# Sheet1.net
KiCad netlist of a schematic drawn in Altium Designer
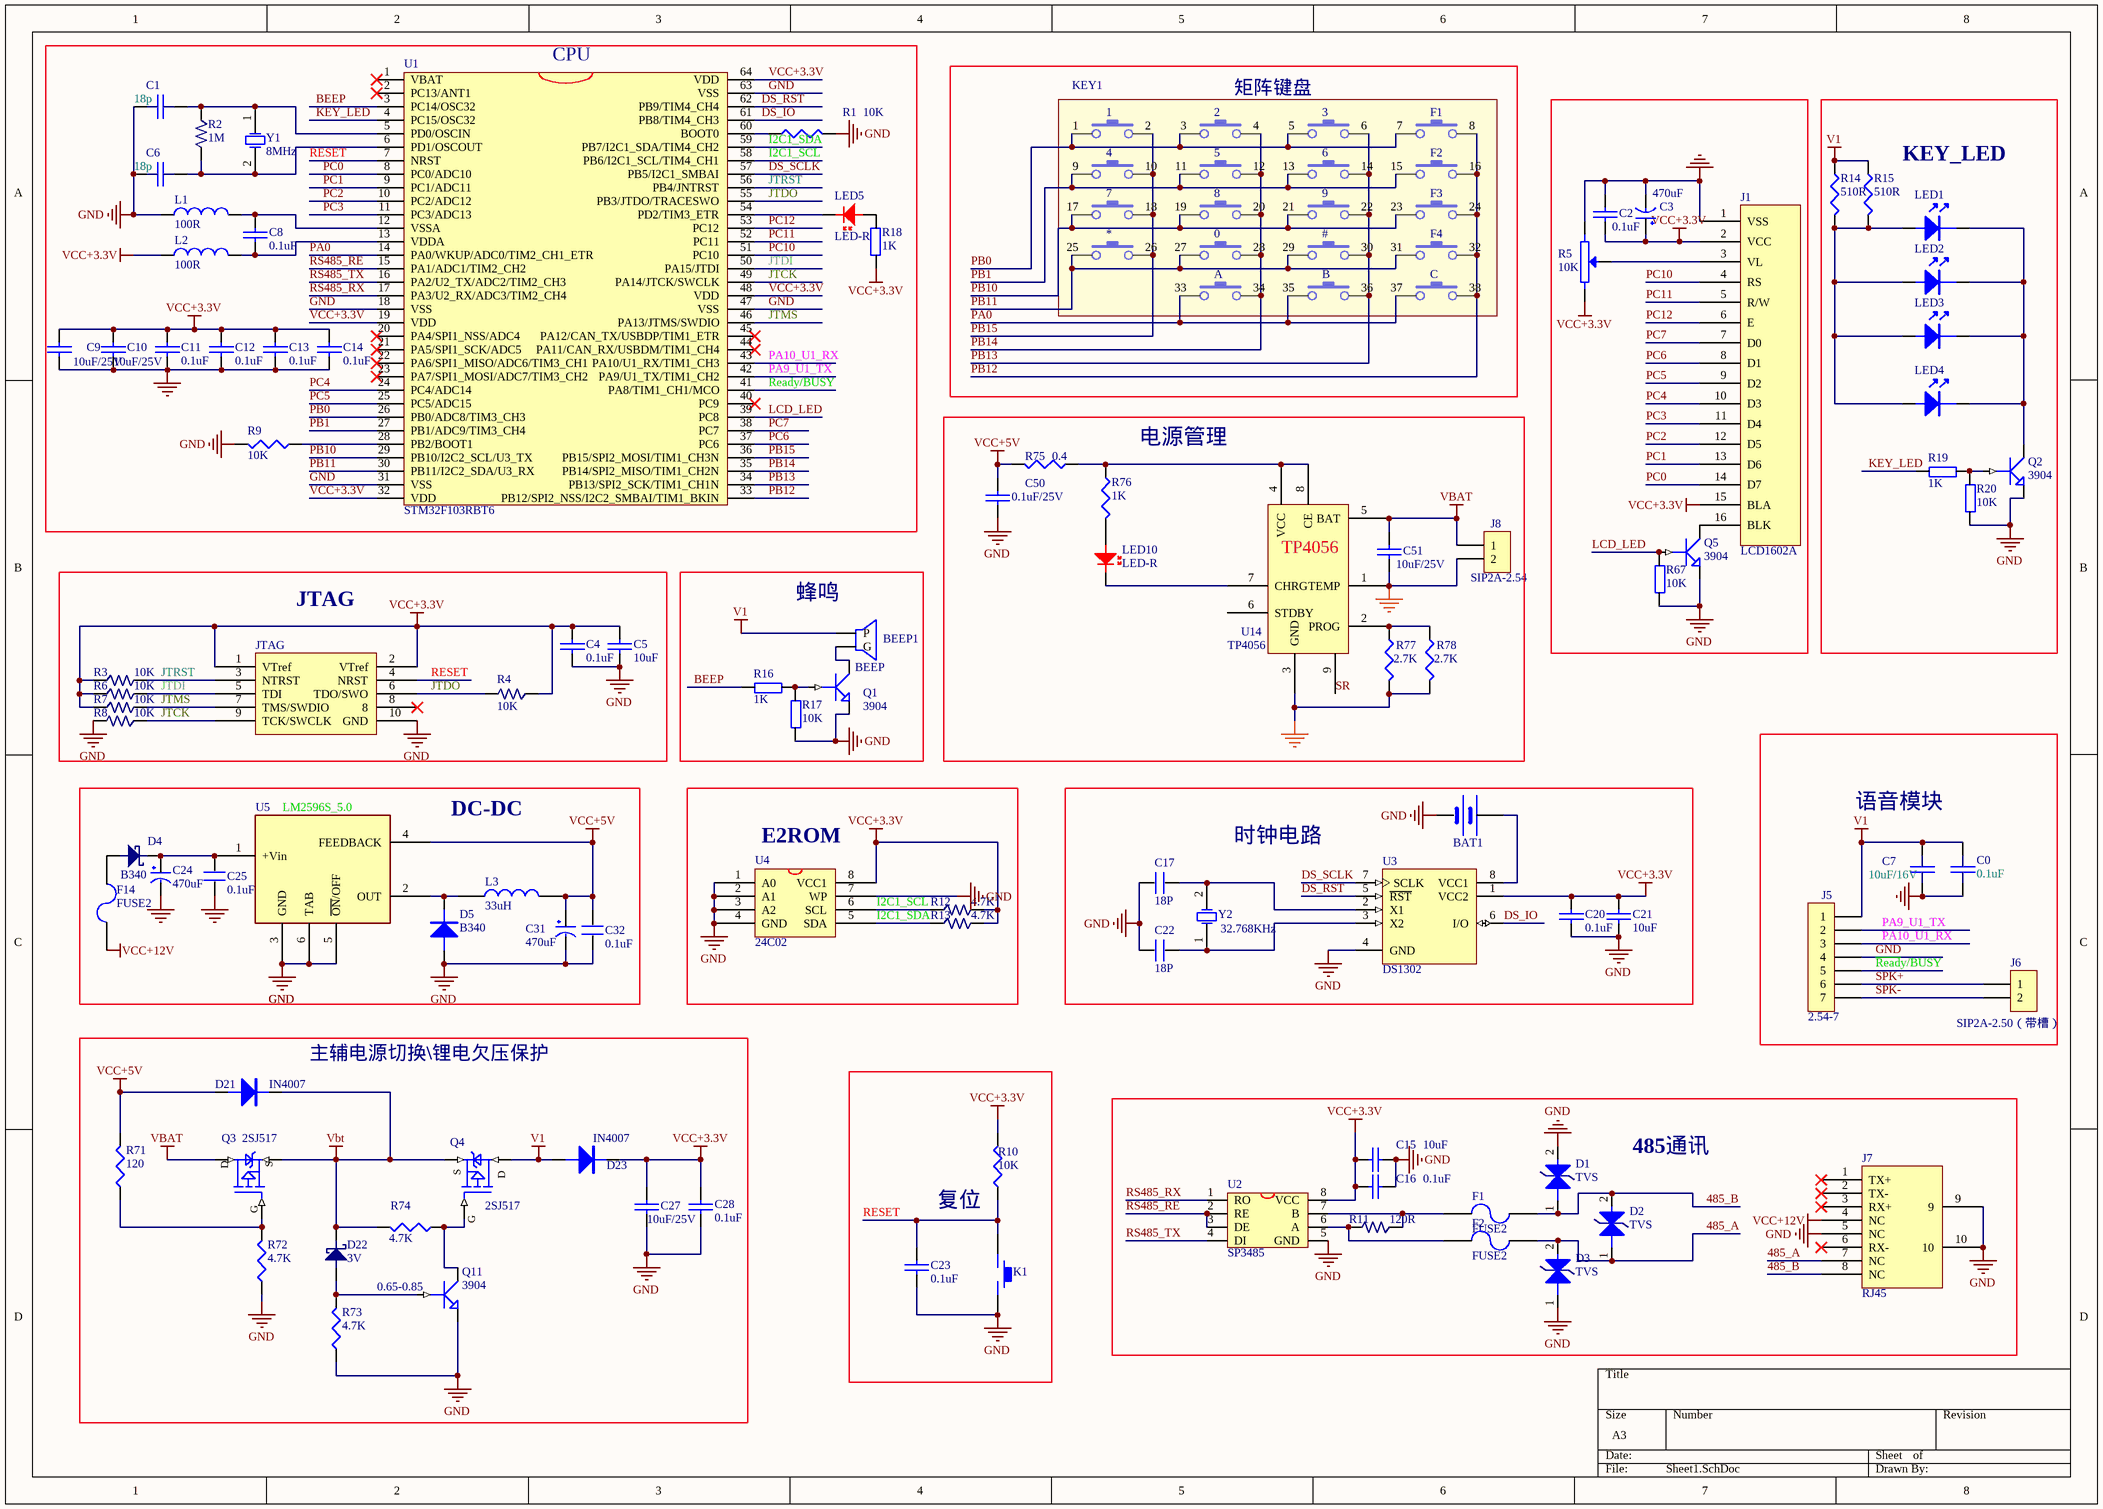
[diagram p0: Sheet1.SchDoc]

(export (version "E")
  (design (tool "Eeschema 10.0.6"))
  (components
    (comp (ref "BAT1") (value "BATT") (footprint "CR1220") (libsource (lib "mylib") (part "BAT")))
    (comp (ref "BEEP1") (value "BEEP") (footprint "BEEP-12W") (libsource (lib "mylib") (part "BEEP")))
    (comp (ref "C0")
      (value "0.1uF")
      (footprint "0603")
      (description "陶瓷电容")
      (libsource (lib "8CF_V6") (part "CAP"))
    )
    (comp (ref "C1")
      (value "18p")
      (footprint "0603")
      (description "陶瓷电容")
      (libsource (lib "8CF_V6") (part "CAP"))
    )
    (comp (ref "C2") (value "0.1uF") (footprint "0603") (libsource (lib "INSPUR_SCH") (part "CAP")))
    (comp (ref "C3") (value "470uF") (footprint "RB3.5-w") (libsource (lib "") (part "CAP_1")))
    (comp (ref "C4") (value "0.1uF") (footprint "0603") (libsource (lib "INSPUR_SCH") (part "CAP")))
    (comp (ref "C5") (value "10uF") (footprint "0805") (libsource (lib "INSPUR_SCH") (part "CAP")))
    (comp (ref "C6")
      (value "18p")
      (footprint "0603")
      (description "陶瓷电容")
      (libsource (lib "8CF_V6") (part "CAP"))
    )
    (comp (ref "C7")
      (value "10uF/16V")
      (footprint "0805")
      (description "陶瓷电容")
      (libsource (lib "8CF_V6") (part "CAP"))
    )
    (comp (ref "C8") (value "0.1uF") (footprint "0603") (libsource (lib "INSPUR_SCH") (part "CAP")))
    (comp (ref "C9") (value "10uF/25V") (footprint "0805") (libsource (lib "*") (part "CAP")))
    (comp (ref "C10") (value "10uF/25V") (footprint "0805") (libsource (lib "*") (part "CAP")))
    (comp (ref "C11") (value "0.1uF") (footprint "0603") (libsource (lib "*") (part "CAP")))
    (comp (ref "C12") (value "0.1uF") (footprint "0603") (libsource (lib "INSPUR_SCH") (part "CAP")))
    (comp (ref "C13") (value "0.1uF") (footprint "0603") (libsource (lib "INSPUR_SCH") (part "CAP")))
    (comp (ref "C14") (value "0.1uF") (footprint "0603") (libsource (lib "INSPUR_SCH") (part "CAP")))
    (comp (ref "C15") (value "10uF") (footprint "0805") (libsource (lib "INSPUR_SCH") (part "CAP")))
    (comp (ref "C16") (value "0.1uF") (footprint "0603") (libsource (lib "INSPUR_SCH") (part "CAP")))
    (comp (ref "C17") (value "18P") (footprint "0603") (libsource (lib "mylib") (part "C")))
    (comp (ref "C20") (value "0.1uF") (footprint "0603") (libsource (lib "INSPUR_SCH") (part "CAP")))
    (comp (ref "C21") (value "10uF") (footprint "0805") (libsource (lib "INSPUR_SCH") (part "CAP")))
    (comp (ref "C22") (value "18P") (footprint "0603") (libsource (lib "mylib") (part "C")))
    (comp (ref "C23") (value "0.1uF") (footprint "0603") (libsource (lib "INSPUR_SCH") (part "CAP")))
    (comp (ref "C24") (value "470uF") (footprint "RB3.5-w") (libsource (lib "战舰STM32开发板底板") (part "CAP")))
    (comp (ref "C25") (value "0.1uF") (footprint "0603") (libsource (lib "mylib") (part "C")))
    (comp (ref "C27") (value "10uF/25V") (footprint "0805") (libsource (lib "*") (part "CAP")))
    (comp (ref "C28") (value "0.1uF") (footprint "0805") (libsource (lib "INSPUR_SCH") (part "CAP")))
    (comp (ref "C31") (value "470uF") (footprint "RB3.5-w") (libsource (lib "战舰STM32开发板底板") (part "CAP")))
    (comp (ref "C32") (value "0.1uF") (footprint "0603") (libsource (lib "mylib") (part "C")))
    (comp (ref "C50") (value "0.1uF/25V") (footprint "0603") (libsource (lib "*") (part "CAP")))
    (comp (ref "C51") (value "10uF/25V") (footprint "0805") (libsource (lib "*") (part "CAP")))
    (comp (ref "D1")
      (value "TVS")
      (footprint "SMB")
      (description "SMBJ12CA")
      (libsource (lib "INSPUR_SCH") (part "TVS"))
    )
    (comp (ref "D2")
      (value "TVS")
      (footprint "SMB")
      (description "SMBJ12CA")
      (libsource (lib "INSPUR_SCH") (part "TVS"))
    )
    (comp (ref "D3")
      (value "TVS")
      (footprint "SMB")
      (description "SMBJ12CA")
      (libsource (lib "INSPUR_SCH") (part "TVS"))
    )
    (comp (ref "D4")
      (value "B340")
      (footprint "SMB")
      (description "肖特基二极管")
      (libsource (lib "mylib") (part "1N5824(SS54)"))
    )
    (comp (ref "D5") (value "B340") (footprint "SMB") (libsource (lib "INSPUR_SCH") (part "DIODE")))
    (comp (ref "D21")
      (value "IN4007")
      (footprint "SMA(DO-214AC)")
      (libsource (lib "INSPUR_SCH") (part "DIODE"))
    )
    (comp (ref "D22")
      (value "3V")
      (footprint "sod-123")
      (description "3V稳压管")
      (libsource (lib "mylib") (part "1N5824(SS54)"))
    )
    (comp (ref "D23") (value "IN4007") (footprint "SMB") (libsource (lib "INSPUR_SCH") (part "DIODE")))
    (comp (ref "F1")
      (value "FUSE2")
      (footprint "0805")
      (description "SMD0805P010TS")
      (libsource (lib "INSPUR_SCH") (part "FUSE2"))
    )
    (comp (ref "F2")
      (value "FUSE2")
      (footprint "0805")
      (description "SMD0805P010TS")
      (libsource (lib "INSPUR_SCH") (part "FUSE2"))
    )
    (comp (ref "F14")
      (value "FUSE2")
      (footprint "FUSE-RL60-050")
      (description "RL60-050")
      (libsource (lib "INSPUR_SCH") (part "FUSE2"))
    )
    (comp (ref "J1")
      (value "LCD1602A")
      (footprint "LCD-1602A")
      (libsource (lib "INSPUR_SCH") (part "LCD1602A"))
    )
    (comp (ref "J2") (value "JTAG") (footprint "JTAG_10") (libsource (lib "mylib") (part "JTAG_10")))
    (comp (ref "J5") (value "2.54-7") (footprint "SYN6288") (libsource (lib "INSPUR_SCH") (part "2.54-7")))
    (comp (ref "J6")
      (value "SIP2A-2.50（带槽）")
      (footprint "2.54")
      (libsource (lib "INSPUR_SCH") (part "SIP2A-2.50（带槽）"))
    )
    (comp (ref "J7") (value "RJ45") (footprint "RJ45-1") (libsource (lib "INSPUR_SCH") (part "RJ45")))
    (comp (ref "J8") (value "SIP2A-2.54") (footprint "2.54") (libsource (lib "*") (part "SIP2A-2.50（带槽）")))
    (comp (ref "K1") (value "KEY_M") (footprint "KEY_M") (libsource (lib "战舰STM32开发板底板") (part "KEY_M")))
    (comp (ref "KEY1") (value "SW-17") (footprint "KEY-17") (libsource (lib "INSPUR_SCH") (part "SW-17")))
    (comp (ref "L1") (value "100R") (footprint "0805") (libsource (lib "INSPUR_SCH") (part "INDUCTOR")))
    (comp (ref "L2") (value "100R") (footprint "0805") (libsource (lib "INSPUR_SCH") (part "INDUCTOR")))
    (comp (ref "L3") (value "33uH") (footprint "INDUCTOR-1212") (libsource (lib "mylib") (part "INDUCTOR")))
    (comp (ref "LED1")
      (value "~")
      (footprint "LED-0805")
      (description "蓝色LED")
      (libsource (lib "INSPUR_SCH") (part "LED"))
    )
    (comp (ref "LED2")
      (value "~")
      (footprint "LED-0805")
      (description "蓝色LED")
      (libsource (lib "INSPUR_SCH") (part "LED"))
    )
    (comp (ref "LED3")
      (value "~")
      (footprint "LED-0805")
      (description "蓝色LED")
      (libsource (lib "INSPUR_SCH") (part "LED"))
    )
    (comp (ref "LED4")
      (value "~")
      (footprint "LED-0805")
      (description "蓝色LED")
      (libsource (lib "INSPUR_SCH") (part "LED"))
    )
    (comp (ref "LED5")
      (value "LED-R")
      (footprint "LED-0805")
      (description "绿色LED")
      (libsource (lib "mylib") (part "LED-RED"))
    )
    (comp (ref "LED10")
      (value "LED-R")
      (footprint "LED-0805")
      (description "红色LED")
      (libsource (lib "mylib") (part "LED-RED"))
    )
    (comp (ref "Q1") (value "3904") (footprint "SOT-23") (libsource (lib "INSPUR_SCH") (part "NPN1")))
    (comp (ref "Q2") (value "3904") (footprint "SOT-23") (libsource (lib "INSPUR_SCH") (part "NPN1")))
    (comp (ref "Q3") (value "2SJ517") (footprint "SOT-89") (libsource (lib "*") (part "MOSFET P_1")))
    (comp (ref "Q4") (value "2SJ517") (footprint "SOT-89") (libsource (lib "*") (part "MOSFET P_1")))
    (comp (ref "Q5") (value "3904") (footprint "SOT-23") (libsource (lib "INSPUR_SCH") (part "NPN1")))
    (comp (ref "Q11") (value "3904") (footprint "SOT-23") (libsource (lib "INSPUR_SCH") (part "NPN1")))
    (comp (ref "R1") (value "10K") (footprint "0603") (libsource (lib "INSPUR_SCH") (part "RES1")))
    (comp (ref "R2")
      (value "1M")
      (footprint "0603")
      (description "高精度电阻")
      (libsource (lib "8CF_V6") (part "RES-1%"))
    )
    (comp (ref "R3")
      (value "10K")
      (footprint "0603")
      (description "高精度电阻")
      (libsource (lib "8CF_V6") (part "RES-1%"))
    )
    (comp (ref "R4")
      (value "10K")
      (footprint "0603")
      (description "高精度电阻")
      (libsource (lib "8CF_V6") (part "RES-1%"))
    )
    (comp (ref "R5") (value "10K") (footprint "RM065-V1") (libsource (lib "INSPUR_SCH") (part "POT2")))
    (comp (ref "R6")
      (value "10K")
      (footprint "0603")
      (description "高精度电阻")
      (libsource (lib "8CF_V6") (part "RES-1%"))
    )
    (comp (ref "R7")
      (value "10K")
      (footprint "0603")
      (description "高精度电阻")
      (libsource (lib "8CF_V6") (part "RES-1%"))
    )
    (comp (ref "R8")
      (value "10K")
      (footprint "0603")
      (description "高精度电阻")
      (libsource (lib "8CF_V6") (part "RES-1%"))
    )
    (comp (ref "R9") (value "10K") (footprint "0603") (libsource (lib "INSPUR_SCH") (part "RES1")))
    (comp (ref "R10") (value "10K") (footprint "0603") (libsource (lib "INSPUR_SCH") (part "RES1")))
    (comp (ref "R11")
      (value "120R")
      (footprint "0603")
      (description "高精度电阻")
      (libsource (lib "8CF_V6") (part "RES-1%"))
    )
    (comp (ref "R12")
      (value "4.7K")
      (footprint "0603")
      (description "高精度电阻")
      (libsource (lib "8CF_V6") (part "RES-1%"))
    )
    (comp (ref "R13")
      (value "4.7K")
      (footprint "0603")
      (description "高精度电阻")
      (libsource (lib "8CF_V6") (part "RES-1%"))
    )
    (comp (ref "R14") (value "510R") (footprint "0805") (libsource (lib "INSPUR_SCH") (part "RES1")))
    (comp (ref "R15") (value "510R") (footprint "0805") (libsource (lib "INSPUR_SCH") (part "RES1")))
    (comp (ref "R16") (value "1K") (footprint "0603") (libsource (lib "mylib") (part "R")))
    (comp (ref "R17") (value "10K") (footprint "0603") (libsource (lib "mylib") (part "R")))
    (comp (ref "R18") (value "1K") (footprint "0603") (libsource (lib "mylib") (part "Res")))
    (comp (ref "R19") (value "1K") (footprint "0805") (libsource (lib "mylib") (part "R")))
    (comp (ref "R20") (value "10K") (footprint "0805") (libsource (lib "mylib") (part "R")))
    (comp (ref "R67") (value "10K") (footprint "0805") (libsource (lib "mylib") (part "R")))
    (comp (ref "R71")
      (value "120")
      (footprint "0805")
      (description "Resistor")
      (libsource (lib "*") (part "RESISTOR"))
    )
    (comp (ref "R72")
      (value "4.7K")
      (footprint "0805")
      (description "Resistor")
      (libsource (lib "*") (part "RESISTOR"))
    )
    (comp (ref "R73")
      (value "4.7K")
      (footprint "0805")
      (description "Resistor")
      (libsource (lib "*") (part "RESISTOR"))
    )
    (comp (ref "R74")
      (value "4.7K")
      (footprint "0805")
      (description "Resistor")
      (libsource (lib "*") (part "RESISTOR"))
    )
    (comp (ref "R75") (value "0.4") (footprint "1206") (libsource (lib "*") (part "RES1")))
    (comp (ref "R76") (value "1K") (footprint "0603") (libsource (lib "*") (part "RES1")))
    (comp (ref "R77") (value "2.7K") (footprint "0603") (libsource (lib "*") (part "RES1")))
    (comp (ref "R78") (value "2.7K") (footprint "0603") (libsource (lib "*") (part "RES1")))
    (comp (ref "U1")
      (value "STM32F103RBT6")
      (footprint "mylib:LQFP64_N")
      (libsource (lib "mylib") (part "STM32F103RBT6"))
    )
    (comp (ref "U2") (value "SP3485") (footprint "SOP-8") (libsource (lib "mylib") (part "MAX3485")))
    (comp (ref "U3")
      (value "DS1302")
      (footprint "SOP-8")
      (description "实时时钟")
      (libsource (lib "mylib") (part "DS1302"))
    )
    (comp (ref "U4") (value "24C02") (footprint "SO-8") (libsource (lib "战舰STM32开发板底板") (part "24C256")))
    (comp (ref "U5")
      (value "LM2596S_5.0")
      (footprint "TO-263-5")
      (description "3A开关电源芯片")
      (libsource (lib "Zhuangzaiji") (part "LM2596S_5.0"))
    )
    (comp (ref "U14") (value "TP4056") (footprint "SO8E") (libsource (lib "*") (part "TP4056")))
    (comp (ref "Y1")
      (value "8MHz")
      (footprint "XTAL_US")
      (description "Crystal Oscillator")
      (fields (field (name "PUBLISHER") "Altium Limited"))
      (libsource (lib "mylib") (part "XTAL"))
    )
    (comp (ref "Y2")
      (value "32.768KHz")
      (footprint "cs-308")
      (description "Crystal Oscillator")
      (fields (field (name "PUBLISHER") "Altium Limited"))
      (libsource (lib "mylib") (part "XTAL"))
    )
  )
  (nets
    (net (code "1") (name "/485_A") (class "Default")
      (node (ref "D2") (pin "1") (pinfunction "A_1") (pintype "passive"))
      (node (ref "D3") (pin "2") (pinfunction "K_2") (pintype "passive"))
      (node (ref "F2") (pin "2") (pinfunction "2_2") (pintype "passive"))
      (node (ref "J7") (pin "7") (pinfunction "NC_7") (pintype "passive"))
    )
    (net (code "2") (name "/485_B") (class "Default")
      (node (ref "D1") (pin "1") (pinfunction "A_1") (pintype "passive"))
      (node (ref "D2") (pin "2") (pinfunction "K_2") (pintype "passive"))
      (node (ref "F1") (pin "2") (pinfunction "2_2") (pintype "passive"))
      (node (ref "J7") (pin "8") (pinfunction "NC_8") (pintype "passive"))
    )
    (net (code "3") (name "/BEEP") (class "Default")
      (node (ref "R16") (pin "1") (pintype "passive"))
      (node (ref "U1") (pin "3") (pinfunction "PC14/OSC32_3") (pintype "passive"))
    )
    (net (code "4") (name "/DS_IO") (class "Default")
      (node (ref "U1") (pin "61") (pinfunction "PB8/TIM4_CH3_61") (pintype "passive"))
      (node (ref "U3") (pin "6") (pinfunction "I/O_6") (pintype "bidirectional"))
    )
    (net (code "5") (name "/DS_RST") (class "Default")
      (node (ref "U1") (pin "62") (pinfunction "PB9/TIM4_CH4_62") (pintype "passive"))
      (node (ref "U3") (pin "5") (pinfunction "~{RST}_5") (pintype "input"))
    )
    (net (code "6") (name "/DS_SCLK") (class "Default")
      (node (ref "U1") (pin "57") (pinfunction "PB5/I2C1_SMBAI_57") (pintype "passive"))
      (node (ref "U3") (pin "7") (pinfunction "SCLK_7") (pintype "input"))
    )
    (net (code "7") (name "/I2C1_SCL") (class "Default")
      (node (ref "R12") (pin "1") (pintype "passive"))
      (node (ref "U1") (pin "58") (pinfunction "PB6/I2C1_SCL/TIM4_CH1_58") (pintype "passive"))
      (node (ref "U4") (pin "6") (pinfunction "SCL_6") (pintype "passive"))
    )
    (net (code "8") (name "/I2C1_SDA") (class "Default")
      (node (ref "R13") (pin "1") (pintype "passive"))
      (node (ref "U1") (pin "59") (pinfunction "PB7/I2C1_SDA/TIM4_CH2_59") (pintype "passive"))
      (node (ref "U4") (pin "5") (pinfunction "SDA_5") (pintype "passive"))
    )
    (net (code "9") (name "/JTCK") (class "Default")
      (node (ref "J2") (pin "9") (pinfunction "TCK/SWCLK_9") (pintype "passive"))
      (node (ref "R8") (pin "1") (pintype "passive"))
      (node (ref "U1") (pin "49") (pinfunction "PA14/JTCK/SWCLK_49") (pintype "passive"))
    )
    (net (code "10") (name "/JTDI") (class "Default")
      (node (ref "J2") (pin "5") (pinfunction "TDI_5") (pintype "passive"))
      (node (ref "R6") (pin "2") (pintype "passive"))
      (node (ref "U1") (pin "50") (pinfunction "PA15/JTDI_50") (pintype "passive"))
    )
    (net (code "11") (name "/JTDO") (class "Default")
      (node (ref "J2") (pin "6") (pinfunction "TDO/SWO_6") (pintype "passive"))
      (node (ref "R4") (pin "2") (pintype "passive"))
      (node (ref "U1") (pin "55") (pinfunction "PB3/JTDO/TRACESWO_55") (pintype "passive"))
    )
    (net (code "12") (name "/JTMS") (class "Default")
      (node (ref "J2") (pin "7") (pinfunction "TMS/SWDIO_7") (pintype "passive"))
      (node (ref "R7") (pin "2") (pintype "passive"))
      (node (ref "U1") (pin "46") (pinfunction "PA13/JTMS/SWDIO_46") (pintype "passive"))
    )
    (net (code "13") (name "/JTRST") (class "Default")
      (node (ref "J2") (pin "3") (pinfunction "NTRST_3") (pintype "passive"))
      (node (ref "R3") (pin "2") (pintype "passive"))
      (node (ref "U1") (pin "56") (pinfunction "PB4/JNTRST_56") (pintype "passive"))
    )
    (net (code "14") (name "/KEY_LED") (class "Default")
      (node (ref "R19") (pin "1") (pintype "passive"))
      (node (ref "U1") (pin "4") (pinfunction "PC15/OSC32_4") (pintype "passive"))
    )
    (net (code "15") (name "/LCD_LED") (class "Default")
      (node (ref "Q5") (pin "1") (pinfunction "B_1") (pintype "input"))
      (node (ref "R67") (pin "2") (pintype "passive"))
      (node (ref "U1") (pin "39") (pinfunction "PC8_39") (pintype "passive"))
    )
    (net (code "16") (name "/PA0") (class "Default")
      (node (ref "KEY1") (pin "33") (pinfunction "33_33") (pintype "passive"))
      (node (ref "KEY1") (pin "35") (pinfunction "35_35") (pintype "passive"))
      (node (ref "KEY1") (pin "37") (pinfunction "37_37") (pintype "passive"))
      (node (ref "U1") (pin "14") (pinfunction "PA0/WKUP/ADC0/TIM2_CH1_ETR_14") (pintype "passive"))
    )
    (net (code "17") (name "/PA9_U1_TX") (class "Default")
      (node (ref "J5") (pin "2") (pinfunction "2_2") (pintype "passive"))
      (node (ref "U1") (pin "42") (pinfunction "PA9/U1_TX/TIM1_CH2_42") (pintype "passive"))
    )
    (net (code "18") (name "/PA10_U1_RX") (class "Default")
      (node (ref "J5") (pin "3") (pinfunction "3_3") (pintype "passive"))
      (node (ref "U1") (pin "43") (pinfunction "PA10/U1_RX/TIM1_CH3_43") (pintype "passive"))
    )
    (net (code "19") (name "/PB0") (class "Default")
      (node (ref "KEY1") (pin "1") (pintype "passive"))
      (node (ref "KEY1") (pin "3") (pinfunction "3_3") (pintype "passive"))
      (node (ref "KEY1") (pin "5") (pinfunction "5_5") (pintype "passive"))
      (node (ref "KEY1") (pin "7") (pinfunction "7_7") (pintype "passive"))
      (node (ref "U1") (pin "26") (pinfunction "PB0/ADC8/TIM3_CH3_26") (pintype "passive"))
    )
    (net (code "20") (name "/PB1") (class "Default")
      (node (ref "KEY1") (pin "11") (pinfunction "11_11") (pintype "passive"))
      (node (ref "KEY1") (pin "13") (pinfunction "13_13") (pintype "passive"))
      (node (ref "KEY1") (pin "15") (pinfunction "15_15") (pintype "passive"))
      (node (ref "KEY1") (pin "9") (pinfunction "9_9") (pintype "passive"))
      (node (ref "U1") (pin "27") (pinfunction "PB1/ADC9/TIM3_CH4_27") (pintype "passive"))
    )
    (net (code "21") (name "/PB10") (class "Default")
      (node (ref "KEY1") (pin "17") (pinfunction "17_17") (pintype "passive"))
      (node (ref "KEY1") (pin "19") (pinfunction "19_19") (pintype "passive"))
      (node (ref "KEY1") (pin "21") (pinfunction "21_21") (pintype "passive"))
      (node (ref "KEY1") (pin "23") (pinfunction "23_23") (pintype "passive"))
      (node (ref "U1") (pin "29") (pinfunction "PB10/I2C2_SCL/U3_TX_29") (pintype "passive"))
    )
    (net (code "22") (name "/PB11") (class "Default")
      (node (ref "KEY1") (pin "25") (pinfunction "25_25") (pintype "passive"))
      (node (ref "KEY1") (pin "27") (pinfunction "27_27") (pintype "passive"))
      (node (ref "KEY1") (pin "29") (pinfunction "29_29") (pintype "passive"))
      (node (ref "KEY1") (pin "31") (pinfunction "31_31") (pintype "passive"))
      (node (ref "U1") (pin "30") (pinfunction "PB11/I2C2_SDA/U3_RX_30") (pintype "passive"))
    )
    (net (code "23") (name "/PB12") (class "Default")
      (node (ref "KEY1") (pin "16") (pinfunction "16_16") (pintype "passive"))
      (node (ref "KEY1") (pin "24") (pinfunction "24_24") (pintype "passive"))
      (node (ref "KEY1") (pin "32") (pinfunction "32_32") (pintype "passive"))
      (node (ref "KEY1") (pin "38") (pinfunction "38_38") (pintype "passive"))
      (node (ref "KEY1") (pin "8") (pinfunction "8_8") (pintype "passive"))
      (node (ref "U1") (pin "33") (pinfunction "PB12/SPI2_NSS/I2C2_SMBAI/TIM1_BKIN_33") (pintype "passive"))
    )
    (net (code "24") (name "/PB13") (class "Default")
      (node (ref "KEY1") (pin "14") (pinfunction "14_14") (pintype "passive"))
      (node (ref "KEY1") (pin "22") (pinfunction "22_22") (pintype "passive"))
      (node (ref "KEY1") (pin "30") (pinfunction "30_30") (pintype "passive"))
      (node (ref "KEY1") (pin "36") (pinfunction "36_36") (pintype "passive"))
      (node (ref "KEY1") (pin "6") (pinfunction "6_6") (pintype "passive"))
      (node (ref "U1") (pin "34") (pinfunction "PB13/SPI2_SCK/TIM1_CH1N_34") (pintype "passive"))
    )
    (net (code "25") (name "/PB14") (class "Default")
      (node (ref "KEY1") (pin "12") (pinfunction "12_12") (pintype "passive"))
      (node (ref "KEY1") (pin "20") (pinfunction "20_20") (pintype "passive"))
      (node (ref "KEY1") (pin "28") (pinfunction "28_28") (pintype "passive"))
      (node (ref "KEY1") (pin "34") (pinfunction "34_34") (pintype "passive"))
      (node (ref "KEY1") (pin "4") (pinfunction "4_4") (pintype "passive"))
      (node (ref "U1") (pin "35") (pinfunction "PB14/SPI2_MISO/TIM1_CH2N_35") (pintype "passive"))
    )
    (net (code "26") (name "/PB15") (class "Default")
      (node (ref "KEY1") (pin "10") (pinfunction "10_10") (pintype "passive"))
      (node (ref "KEY1") (pin "18") (pinfunction "18_18") (pintype "passive"))
      (node (ref "KEY1") (pin "2") (pinfunction "10_2") (pintype "passive"))
      (node (ref "KEY1") (pin "26") (pinfunction "26_26") (pintype "passive"))
      (node (ref "U1") (pin "36") (pinfunction "PB15/SPI2_MOSI/TIM1_CH3N_36") (pintype "passive"))
    )
    (net (code "27") (name "/PC0") (class "Default")
      (node (ref "J1") (pin "14") (pinfunction "D7_14") (pintype "passive"))
      (node (ref "U1") (pin "8") (pinfunction "PC0/ADC10_8") (pintype "passive"))
    )
    (net (code "28") (name "/PC1") (class "Default")
      (node (ref "J1") (pin "13") (pinfunction "D6_13") (pintype "passive"))
      (node (ref "U1") (pin "9") (pinfunction "PC1/ADC11_9") (pintype "passive"))
    )
    (net (code "29") (name "/PC2") (class "Default")
      (node (ref "J1") (pin "12") (pinfunction "D5_12") (pintype "passive"))
      (node (ref "U1") (pin "10") (pinfunction "PC2/ADC12_10") (pintype "passive"))
    )
    (net (code "30") (name "/PC3") (class "Default")
      (node (ref "J1") (pin "11") (pinfunction "D4_11") (pintype "passive"))
      (node (ref "U1") (pin "11") (pinfunction "PC3/ADC13_11") (pintype "passive"))
    )
    (net (code "31") (name "/PC4") (class "Default")
      (node (ref "J1") (pin "10") (pinfunction "D3_10") (pintype "passive"))
      (node (ref "U1") (pin "24") (pinfunction "PC4/ADC14_24") (pintype "passive"))
    )
    (net (code "32") (name "/PC5") (class "Default")
      (node (ref "J1") (pin "9") (pinfunction "D2_9") (pintype "passive"))
      (node (ref "U1") (pin "25") (pinfunction "PC5/ADC15_25") (pintype "passive"))
    )
    (net (code "33") (name "/PC6") (class "Default")
      (node (ref "J1") (pin "8") (pinfunction "D1_8") (pintype "passive"))
      (node (ref "U1") (pin "37") (pinfunction "PC6_37") (pintype "passive"))
    )
    (net (code "34") (name "/PC7") (class "Default")
      (node (ref "J1") (pin "7") (pinfunction "D0_7") (pintype "passive"))
      (node (ref "U1") (pin "38") (pinfunction "PC7_38") (pintype "passive"))
    )
    (net (code "35") (name "/PC10") (class "Default")
      (node (ref "J1") (pin "4") (pinfunction "RS_4") (pintype "passive"))
      (node (ref "U1") (pin "51") (pinfunction "PC10_51") (pintype "passive"))
    )
    (net (code "36") (name "/PC11") (class "Default")
      (node (ref "J1") (pin "5") (pinfunction "R/W_5") (pintype "passive"))
      (node (ref "U1") (pin "52") (pinfunction "PC11_52") (pintype "passive"))
    )
    (net (code "37") (name "/PC12") (class "Default")
      (node (ref "J1") (pin "6") (pinfunction "E_6") (pintype "passive"))
      (node (ref "U1") (pin "53") (pinfunction "PC12_53") (pintype "passive"))
    )
    (net (code "38") (name "/RESET") (class "Default")
      (node (ref "C23") (pin "1") (pinfunction "1_1") (pintype "passive"))
      (node (ref "J2") (pin "4") (pinfunction "NRST_4") (pintype "passive"))
      (node (ref "K1") (pin "1") (pinfunction "1_1") (pintype "passive"))
      (node (ref "R10") (pin "1") (pinfunction "1_1") (pintype "passive"))
      (node (ref "U1") (pin "7") (pinfunction "NRST_7") (pintype "passive"))
    )
    (net (code "39") (name "/RS485_RE") (class "Default")
      (node (ref "U1") (pin "15") (pinfunction "PA1/ADC1/TIM2_CH2_15") (pintype "passive"))
      (node (ref "U2") (pin "2") (pinfunction "RE_2") (pintype "passive"))
      (node (ref "U2") (pin "3") (pinfunction "DE_3") (pintype "passive"))
    )
    (net (code "40") (name "/RS485_RX") (class "Default")
      (node (ref "U1") (pin "17") (pinfunction "PA3/U2_RX/ADC3/TIM2_CH4_17") (pintype "passive"))
      (node (ref "U2") (pin "1") (pinfunction "RO_1") (pintype "passive"))
    )
    (net (code "41") (name "/RS485_TX") (class "Default")
      (node (ref "U1") (pin "16") (pinfunction "PA2/U2_TX/ADC2/TIM2_CH3_16") (pintype "passive"))
      (node (ref "U2") (pin "4") (pinfunction "DI_4") (pintype "passive"))
    )
    (net (code "42") (name "/SPK+") (class "Default")
      (node (ref "J5") (pin "6") (pinfunction "6_6") (pintype "passive"))
      (node (ref "J6") (pin "1") (pinfunction "1_1") (pintype "passive"))
    )
    (net (code "43") (name "/SPK-") (class "Default")
      (node (ref "J5") (pin "7") (pinfunction "7_7") (pintype "passive"))
      (node (ref "J6") (pin "2") (pinfunction "2_2") (pintype "passive"))
    )
    (net (code "44") (name "/SR") (class "Default") (node (ref "U14") (pin "9") (pintype "passive")))
    (net (code "45") (name "/~{Read}y{slash}BUSY") (class "Default")
      (node (ref "J5") (pin "5") (pinfunction "5_5") (pintype "passive"))
      (node (ref "U1") (pin "41") (pinfunction "PA8/TIM1_CH1/MCO_41") (pintype "passive"))
    )
    (net (code "46") (name "GND") (class "Default")
      (node (ref "BAT1") (pin "2") (pinfunction "GND_2") (pintype "passive"))
      (node (ref "C0") (pin "1") (pintype "passive"))
      (node (ref "C1") (pin "2") (pintype "passive"))
      (node (ref "C10") (pin "1") (pinfunction "1_1") (pintype "passive"))
      (node (ref "C11") (pin "1") (pinfunction "1_1") (pintype "passive"))
      (node (ref "C12") (pin "1") (pinfunction "1_1") (pintype "passive"))
      (node (ref "C13") (pin "1") (pinfunction "1_1") (pintype "passive"))
      (node (ref "C14") (pin "1") (pinfunction "1_1") (pintype "passive"))
      (node (ref "C15") (pin "2") (pinfunction "2_2") (pintype "passive"))
      (node (ref "C16") (pin "2") (pinfunction "2_2") (pintype "passive"))
      (node (ref "C17") (pin "1") (pintype "passive"))
      (node (ref "C2") (pin "2") (pinfunction "2_2") (pintype "passive"))
      (node (ref "C20") (pin "1") (pinfunction "1_1") (pintype "passive"))
      (node (ref "C21") (pin "1") (pinfunction "1_1") (pintype "passive"))
      (node (ref "C22") (pin "1") (pintype "passive"))
      (node (ref "C23") (pin "2") (pinfunction "2_2") (pintype "passive"))
      (node (ref "C24") (pin "2") (pinfunction "GND_2") (pintype "passive"))
      (node (ref "C25") (pin "1") (pintype "passive"))
      (node (ref "C27") (pin "2") (pinfunction "2_2") (pintype "passive"))
      (node (ref "C28") (pin "2") (pinfunction "2_2") (pintype "passive"))
      (node (ref "C3") (pin "2") (pinfunction "GND_2") (pintype "passive"))
      (node (ref "C31") (pin "2") (pinfunction "GND_2") (pintype "passive"))
      (node (ref "C32") (pin "1") (pintype "passive"))
      (node (ref "C4") (pin "1") (pinfunction "1_1") (pintype "passive"))
      (node (ref "C5") (pin "1") (pinfunction "1_1") (pintype "passive"))
      (node (ref "C50") (pin "2") (pinfunction "2_2") (pintype "passive"))
      (node (ref "C51") (pin "2") (pinfunction "2_2") (pintype "passive"))
      (node (ref "C6") (pin "2") (pintype "passive"))
      (node (ref "C7") (pin "1") (pintype "passive"))
      (node (ref "C9") (pin "1") (pinfunction "1_1") (pintype "passive"))
      (node (ref "D1") (pin "2") (pinfunction "K_2") (pintype "passive"))
      (node (ref "D3") (pin "1") (pinfunction "A_1") (pintype "passive"))
      (node (ref "D5") (pin "1") (pinfunction "A_1") (pintype "passive"))
      (node (ref "J1") (pin "1") (pinfunction "VSS_1") (pintype "passive"))
      (node (ref "J2") (pin "10") (pinfunction "GND_10") (pintype "passive"))
      (node (ref "J5") (pin "4") (pinfunction "4_4") (pintype "passive"))
      (node (ref "J7") (pin "10") (pinfunction "10_10") (pintype "passive"))
      (node (ref "J7") (pin "5") (pinfunction "NC_5") (pintype "passive"))
      (node (ref "J7") (pin "9") (pinfunction "9_9") (pintype "passive"))
      (node (ref "J8") (pin "2") (pinfunction "2_2") (pintype "passive"))
      (node (ref "K1") (pin "2") (pinfunction "2_2") (pintype "passive"))
      (node (ref "L1") (pin "1") (pinfunction "1_1") (pintype "passive"))
      (node (ref "Q1") (pin "2") (pinfunction "E_2") (pintype "passive"))
      (node (ref "Q11") (pin "2") (pinfunction "E_2") (pintype "passive"))
      (node (ref "Q2") (pin "2") (pinfunction "E_2") (pintype "passive"))
      (node (ref "Q5") (pin "2") (pinfunction "E_2") (pintype "passive"))
      (node (ref "R1") (pin "2") (pinfunction "2_2") (pintype "passive"))
      (node (ref "R17") (pin "1") (pintype "passive"))
      (node (ref "R20") (pin "1") (pintype "passive"))
      (node (ref "R5") (pin "1") (pinfunction "1_1") (pintype "passive"))
      (node (ref "R67") (pin "1") (pintype "passive"))
      (node (ref "R72") (pin "1") (pinfunction "1_1") (pintype "passive"))
      (node (ref "R73") (pin "1") (pinfunction "1_1") (pintype "passive"))
      (node (ref "R77") (pin "2") (pinfunction "2_2") (pintype "passive"))
      (node (ref "R78") (pin "2") (pinfunction "2_2") (pintype "passive"))
      (node (ref "R8") (pin "2") (pintype "passive"))
      (node (ref "R9") (pin "2") (pinfunction "2_2") (pintype "passive"))
      (node (ref "U1") (pin "18") (pinfunction "VSS_18") (pintype "passive"))
      (node (ref "U1") (pin "31") (pinfunction "VSS_31") (pintype "passive"))
      (node (ref "U1") (pin "47") (pinfunction "VSS_47") (pintype "passive"))
      (node (ref "U1") (pin "63") (pinfunction "VSS_63") (pintype "passive"))
      (node (ref "U14") (pin "1") (pinfunction "TEMP_1") (pintype "passive"))
      (node (ref "U14") (pin "3") (pinfunction "GND_3") (pintype "passive"))
      (node (ref "U2") (pin "5") (pinfunction "GND_5") (pintype "passive"))
      (node (ref "U3") (pin "4") (pinfunction "GND_4") (pintype "power_in"))
      (node (ref "U4") (pin "1") (pinfunction "A0_1") (pintype "passive"))
      (node (ref "U4") (pin "2") (pinfunction "A1_2") (pintype "passive"))
      (node (ref "U4") (pin "3") (pinfunction "A2_3") (pintype "passive"))
      (node (ref "U4") (pin "4") (pinfunction "GND_4") (pintype "passive"))
      (node (ref "U4") (pin "7") (pinfunction "WP_7") (pintype "passive"))
      (node (ref "U5") (pin "3") (pinfunction "GND_3") (pintype "passive"))
      (node (ref "U5") (pin "5") (pinfunction "~{ON}/OFF_5") (pintype "passive"))
      (node (ref "U5") (pin "6") (pinfunction "TAB_6") (pintype "passive"))
    )
    (net (code "47") (name "Net-(BAT1-VCC)") (class "Default")
      (node (ref "BAT1") (pin "1") (pinfunction "VCC_1") (pintype "passive"))
      (node (ref "U3") (pin "8") (pinfunction "VCC1_8") (pintype "power_in"))
    )
    (net (code "48") (name "Net-(BEEP1-G)") (class "Default")
      (node (ref "BEEP1") (pin "2") (pinfunction "G_2") (pintype "passive"))
      (node (ref "Q1") (pin "3") (pinfunction "C_3") (pintype "passive"))
    )
    (net (code "49") (name "Net-(C24-VCC)") (class "Default")
      (node (ref "C24") (pin "1") (pinfunction "VCC_1") (pintype "passive"))
      (node (ref "C25") (pin "2") (pintype "passive"))
      (node (ref "D4") (pin "2") (pintype "passive"))
      (node (ref "U5") (pin "1") (pinfunction "+Vin_1") (pintype "passive"))
    )
    (net (code "50") (name "Net-(D4-Pad1)") (class "Default")
      (node (ref "D4") (pin "1") (pintype "passive"))
      (node (ref "F14") (pin "2") (pinfunction "2_2") (pintype "passive"))
    )
    (net (code "51") (name "Net-(D5-K)") (class "Default")
      (node (ref "D5") (pin "2") (pinfunction "K_2") (pintype "passive"))
      (node (ref "L3") (pin "1") (pinfunction "1_1") (pintype "passive"))
      (node (ref "U5") (pin "2") (pinfunction "OUT_2") (pintype "passive"))
    )
    (net (code "52") (name "Net-(J1-BLK)") (class "Default")
      (node (ref "J1") (pin "16") (pinfunction "BLK_16") (pintype "passive"))
      (node (ref "Q5") (pin "3") (pinfunction "C_3") (pintype "passive"))
    )
    (net (code "53") (name "Net-(J1-VL)") (class "Default")
      (node (ref "J1") (pin "3") (pinfunction "VL_3") (pintype "passive"))
      (node (ref "R5") (pin "2") (pinfunction "2_2") (pintype "passive"))
    )
    (net (code "54") (name "Net-(LED1-Pad1)") (class "Default")
      (node (ref "LED1") (pin "1") (pinfunction "1_1") (pintype "passive"))
      (node (ref "LED2") (pin "1") (pinfunction "1_1") (pintype "passive"))
      (node (ref "LED3") (pin "1") (pinfunction "1_1") (pintype "passive"))
      (node (ref "LED4") (pin "1") (pinfunction "1_1") (pintype "passive"))
      (node (ref "R14") (pin "2") (pinfunction "2_2") (pintype "passive"))
      (node (ref "R15") (pin "2") (pinfunction "2_2") (pintype "passive"))
    )
    (net (code "55") (name "Net-(LED5-Pad1)") (class "Default")
      (node (ref "LED5") (pin "1") (pintype "passive"))
      (node (ref "R18") (pin "1") (pintype "passive"))
    )
    (net (code "56") (name "Net-(LED10-Pad1)") (class "Default")
      (node (ref "LED10") (pin "1") (pintype "passive"))
      (node (ref "R76") (pin "2") (pinfunction "2_2") (pintype "passive"))
    )
    (net (code "57") (name "Net-(Q1-B)") (class "Default")
      (node (ref "Q1") (pin "1") (pinfunction "B_1") (pintype "input"))
      (node (ref "R16") (pin "2") (pintype "passive"))
      (node (ref "R17") (pin "2") (pintype "passive"))
    )
    (net (code "58") (name "Net-(Q2-B)") (class "Default")
      (node (ref "Q2") (pin "1") (pinfunction "B_1") (pintype "input"))
      (node (ref "R19") (pin "2") (pintype "passive"))
      (node (ref "R20") (pin "2") (pintype "passive"))
    )
    (net (code "59") (name "Net-(Q2-C)") (class "Default")
      (node (ref "LED1") (pin "2") (pinfunction "2_2") (pintype "passive"))
      (node (ref "LED2") (pin "2") (pinfunction "2_2") (pintype "passive"))
      (node (ref "LED3") (pin "2") (pinfunction "2_2") (pintype "passive"))
      (node (ref "LED4") (pin "2") (pinfunction "2_2") (pintype "passive"))
      (node (ref "Q2") (pin "3") (pinfunction "C_3") (pintype "passive"))
    )
    (net (code "60") (name "Net-(Q3-G)") (class "Default")
      (node (ref "Q3") (pin "1") (pinfunction "G_1") (pintype "input"))
      (node (ref "R71") (pin "1") (pinfunction "1_1") (pintype "passive"))
      (node (ref "R72") (pin "2") (pinfunction "2_2") (pintype "passive"))
    )
    (net (code "61") (name "Net-(Q11-B)") (class "Default")
      (node (ref "D22") (pin "1") (pintype "passive"))
      (node (ref "Q11") (pin "1") (pinfunction "B_1") (pintype "input"))
      (node (ref "R73") (pin "2") (pinfunction "2_2") (pintype "passive"))
    )
    (net (code "62") (name "Net-(Q11-C)") (class "Default")
      (node (ref "Q11") (pin "3") (pinfunction "C_3") (pintype "passive"))
      (node (ref "Q4") (pin "1") (pinfunction "G_1") (pintype "input"))
      (node (ref "R74") (pin "1") (pinfunction "1_1") (pintype "passive"))
    )
    (net (code "63") (name "Net-(U1-BOOT0)") (class "Default")
      (node (ref "R1") (pin "1") (pinfunction "1_1") (pintype "passive"))
      (node (ref "U1") (pin "60") (pinfunction "BOOT0_60") (pintype "passive"))
    )
    (net (code "64") (name "Net-(U1-PB2{slash}BOOT1)") (class "Default")
      (node (ref "R9") (pin "1") (pinfunction "1_1") (pintype "passive"))
      (node (ref "U1") (pin "28") (pinfunction "PB2/BOOT1_28") (pintype "passive"))
    )
    (net (code "65") (name "Net-(U1-PD0{slash}OSCIN)") (class "Default")
      (node (ref "C1") (pin "1") (pintype "passive"))
      (node (ref "R2") (pin "1") (pintype "passive"))
      (node (ref "U1") (pin "5") (pinfunction "PD0/OSCIN_5") (pintype "passive"))
      (node (ref "Y1") (pin "1") (pinfunction "OSC1_1") (pintype "passive"))
    )
    (net (code "66") (name "Net-(U1-PD1{slash}OSCOUT)") (class "Default")
      (node (ref "C6") (pin "1") (pintype "passive"))
      (node (ref "R2") (pin "2") (pintype "passive"))
      (node (ref "U1") (pin "6") (pinfunction "PD1/OSCOUT_6") (pintype "passive"))
      (node (ref "Y1") (pin "2") (pinfunction "OSC2_2") (pintype "passive"))
    )
    (net (code "67") (name "Net-(U1-PD2{slash}TIM3_ETR)") (class "Default")
      (node (ref "LED5") (pin "2") (pintype "passive"))
      (node (ref "U1") (pin "54") (pinfunction "PD2/TIM3_ETR_54") (pintype "passive"))
    )
    (net (code "68") (name "Net-(U1-VDDA)") (class "Default")
      (node (ref "C8") (pin "1") (pinfunction "1_1") (pintype "passive"))
      (node (ref "L2") (pin "2") (pinfunction "2_2") (pintype "passive"))
      (node (ref "U1") (pin "13") (pinfunction "VDDA_13") (pintype "passive"))
    )
    (net (code "69") (name "Net-(U1-VSSA)") (class "Default")
      (node (ref "C8") (pin "2") (pinfunction "2_2") (pintype "passive"))
      (node (ref "L1") (pin "2") (pinfunction "2_2") (pintype "passive"))
      (node (ref "U1") (pin "12") (pinfunction "VSSA_12") (pintype "passive"))
    )
    (net (code "70") (name "Net-(U2-A)") (class "Default")
      (node (ref "F2") (pin "1") (pinfunction "1_1") (pintype "passive"))
      (node (ref "R11") (pin "2") (pintype "passive"))
      (node (ref "U2") (pin "6") (pinfunction "A_6") (pintype "passive"))
    )
    (net (code "71") (name "Net-(U2-B)") (class "Default")
      (node (ref "F1") (pin "1") (pinfunction "1_1") (pintype "passive"))
      (node (ref "R11") (pin "1") (pintype "passive"))
      (node (ref "U2") (pin "7") (pinfunction "B_7") (pintype "passive"))
    )
    (net (code "72") (name "Net-(U3-X1)") (class "Default")
      (node (ref "C17") (pin "2") (pintype "passive"))
      (node (ref "U3") (pin "2") (pinfunction "X1_2") (pintype "input"))
      (node (ref "Y2") (pin "2") (pinfunction "OSC2_2") (pintype "passive"))
    )
    (net (code "73") (name "Net-(U3-X2)") (class "Default")
      (node (ref "C22") (pin "2") (pintype "passive"))
      (node (ref "U3") (pin "3") (pinfunction "X2_3") (pintype "input"))
      (node (ref "Y2") (pin "1") (pinfunction "OSC1_1") (pintype "passive"))
    )
    (net (code "74") (name "Net-(U14-CE)") (class "Default")
      (node (ref "R75") (pin "1") (pinfunction "1_1") (pintype "passive"))
      (node (ref "R76") (pin "1") (pinfunction "1_1") (pintype "passive"))
      (node (ref "U14") (pin "4") (pinfunction "VCC_4") (pintype "passive"))
      (node (ref "U14") (pin "8") (pinfunction "CE_8") (pintype "passive"))
    )
    (net (code "75") (name "Net-(U14-CHRG)") (class "Default")
      (node (ref "LED10") (pin "2") (pintype "passive"))
      (node (ref "U14") (pin "7") (pinfunction "CHRG_7") (pintype "passive"))
    )
    (net (code "76") (name "Net-(U14-PROG)") (class "Default")
      (node (ref "R77") (pin "1") (pinfunction "1_1") (pintype "passive"))
      (node (ref "R78") (pin "1") (pinfunction "1_1") (pintype "passive"))
      (node (ref "U14") (pin "2") (pinfunction "PROG_2") (pintype "passive"))
    )
    (net (code "77") (name "V1") (class "Default")
      (node (ref "BEEP1") (pin "1") (pinfunction "P_1") (pintype "passive"))
      (node (ref "C0") (pin "2") (pintype "passive"))
      (node (ref "C7") (pin "2") (pintype "passive"))
      (node (ref "D23") (pin "1") (pinfunction "A_1") (pintype "passive"))
      (node (ref "J5") (pin "1") (pinfunction "1_1") (pintype "passive"))
      (node (ref "Q4") (pin "2") (pinfunction "D_2") (pintype "input"))
      (node (ref "R14") (pin "1") (pinfunction "1_1") (pintype "passive"))
      (node (ref "R15") (pin "1") (pinfunction "1_1") (pintype "passive"))
    )
    (net (code "78") (name "VBAT") (class "Default")
      (node (ref "C51") (pin "1") (pinfunction "1_1") (pintype "passive"))
      (node (ref "J8") (pin "1") (pinfunction "1_1") (pintype "passive"))
      (node (ref "Q3") (pin "2") (pinfunction "D_2") (pintype "input"))
      (node (ref "U14") (pin "5") (pinfunction "BAT_5") (pintype "passive"))
    )
    (net (code "79") (name "VCC+3.3V") (class "Default")
      (node (ref "C10") (pin "2") (pinfunction "2_2") (pintype "passive"))
      (node (ref "C11") (pin "2") (pinfunction "2_2") (pintype "passive"))
      (node (ref "C12") (pin "2") (pinfunction "2_2") (pintype "passive"))
      (node (ref "C13") (pin "2") (pinfunction "2_2") (pintype "passive"))
      (node (ref "C14") (pin "2") (pinfunction "2_2") (pintype "passive"))
      (node (ref "C15") (pin "1") (pinfunction "1_1") (pintype "passive"))
      (node (ref "C16") (pin "1") (pinfunction "1_1") (pintype "passive"))
      (node (ref "C2") (pin "1") (pinfunction "1_1") (pintype "passive"))
      (node (ref "C20") (pin "2") (pinfunction "2_2") (pintype "passive"))
      (node (ref "C21") (pin "2") (pinfunction "2_2") (pintype "passive"))
      (node (ref "C27") (pin "1") (pinfunction "1_1") (pintype "passive"))
      (node (ref "C28") (pin "1") (pinfunction "1_1") (pintype "passive"))
      (node (ref "C3") (pin "1") (pinfunction "VCC_1") (pintype "passive"))
      (node (ref "C4") (pin "2") (pinfunction "2_2") (pintype "passive"))
      (node (ref "C5") (pin "2") (pinfunction "2_2") (pintype "passive"))
      (node (ref "C9") (pin "2") (pinfunction "2_2") (pintype "passive"))
      (node (ref "D23") (pin "2") (pinfunction "K_2") (pintype "passive"))
      (node (ref "J1") (pin "15") (pinfunction "BLA_15") (pintype "passive"))
      (node (ref "J1") (pin "2") (pinfunction "VCC_2") (pintype "passive"))
      (node (ref "J2") (pin "1") (pinfunction "VTref_1") (pintype "passive"))
      (node (ref "J2") (pin "2") (pinfunction "VTref_2") (pintype "passive"))
      (node (ref "L2") (pin "1") (pinfunction "1_1") (pintype "passive"))
      (node (ref "R10") (pin "2") (pinfunction "2_2") (pintype "passive"))
      (node (ref "R12") (pin "2") (pintype "passive"))
      (node (ref "R13") (pin "2") (pintype "passive"))
      (node (ref "R18") (pin "2") (pintype "passive"))
      (node (ref "R3") (pin "1") (pintype "passive"))
      (node (ref "R4") (pin "1") (pintype "passive"))
      (node (ref "R5") (pin "3") (pinfunction "3_3") (pintype "passive"))
      (node (ref "R6") (pin "1") (pintype "passive"))
      (node (ref "R7") (pin "1") (pintype "passive"))
      (node (ref "U1") (pin "19") (pinfunction "VDD_19") (pintype "passive"))
      (node (ref "U1") (pin "32") (pinfunction "VDD_32") (pintype "passive"))
      (node (ref "U1") (pin "48") (pinfunction "VDD_48") (pintype "passive"))
      (node (ref "U1") (pin "64") (pinfunction "VDD_64") (pintype "passive"))
      (node (ref "U2") (pin "8") (pinfunction "VCC_8") (pintype "passive"))
      (node (ref "U3") (pin "1") (pinfunction "VCC2_1") (pintype "power_in"))
      (node (ref "U4") (pin "8") (pinfunction "VCC1_8") (pintype "passive"))
    )
    (net (code "80") (name "VCC+5V") (class "Default")
      (node (ref "C31") (pin "1") (pinfunction "VCC_1") (pintype "passive"))
      (node (ref "C32") (pin "2") (pintype "passive"))
      (node (ref "C50") (pin "1") (pinfunction "1_1") (pintype "passive"))
      (node (ref "D21") (pin "1") (pinfunction "A_1") (pintype "passive"))
      (node (ref "L3") (pin "2") (pinfunction "2_2") (pintype "passive"))
      (node (ref "R71") (pin "2") (pinfunction "2_2") (pintype "passive"))
      (node (ref "R75") (pin "2") (pinfunction "2_2") (pintype "passive"))
      (node (ref "U5") (pin "4") (pinfunction "FEEDBACK_4") (pintype "passive"))
    )
    (net (code "81") (name "VCC+12V") (class "Default")
      (node (ref "F14") (pin "1") (pinfunction "1_1") (pintype "passive"))
      (node (ref "J7") (pin "4") (pinfunction "NC_4") (pintype "passive"))
    )
    (net (code "82") (name "Vbt") (class "Default")
      (node (ref "D21") (pin "2") (pinfunction "K_2") (pintype "passive"))
      (node (ref "D22") (pin "2") (pintype "passive"))
      (node (ref "Q3") (pin "3") (pinfunction "S_3") (pintype "input"))
      (node (ref "Q4") (pin "3") (pinfunction "S_3") (pintype "input"))
      (node (ref "R74") (pin "2") (pinfunction "2_2") (pintype "passive"))
    )
    (net (code "83") (name "unconnected-(J2-Pad8)") (class "Default")
      (node (ref "J2") (pin "8") (pinfunction "8_8") (pintype "passive+no_connect"))
    )
    (net (code "84") (name "unconnected-(J7-RX+-Pad3)") (class "Default")
      (node (ref "J7") (pin "3") (pinfunction "RX+_3") (pintype "passive+no_connect"))
    )
    (net (code "85") (name "unconnected-(J7-RX--Pad6)") (class "Default")
      (node (ref "J7") (pin "6") (pinfunction "RX-_6") (pintype "passive+no_connect"))
    )
    (net (code "86") (name "unconnected-(J7-TX+-Pad1)") (class "Default")
      (node (ref "J7") (pin "1") (pinfunction "TX+_1") (pintype "passive+no_connect"))
    )
    (net (code "87") (name "unconnected-(J7-TX--Pad2)") (class "Default")
      (node (ref "J7") (pin "2") (pinfunction "TX-_2") (pintype "passive+no_connect"))
    )
    (net (code "88") (name "unconnected-(U1-PA4{slash}SPI1_NSS{slash}ADC4-Pad20)") (class "Default")
      (node (ref "U1") (pin "20") (pinfunction "PA4/SPI1_NSS/ADC4_20") (pintype "passive+no_connect"))
    )
    (net (code "89") (name "unconnected-(U1-PA5{slash}SPI1_SCK{slash}ADC5-Pad21)") (class "Default")
      (node (ref "U1") (pin "21") (pinfunction "PA5/SPI1_SCK/ADC5_21") (pintype "passive+no_connect"))
    )
    (net (code "90") (name "unconnected-(U1-PA6{slash}SPI1_MISO{slash}ADC6{slash}TIM3_CH1-Pad22)") (class "Default")
      (node (ref "U1") (pin "22") (pinfunction "PA6/SPI1_MISO/ADC6/TIM3_CH1_22") (pintype "passive+no_connect"))
    )
    (net (code "91") (name "unconnected-(U1-PA7{slash}SPI1_MOSI{slash}ADC7{slash}TIM3_CH2-Pad23)") (class "Default")
      (node (ref "U1") (pin "23") (pinfunction "PA7/SPI1_MOSI/ADC7/TIM3_CH2_23") (pintype "passive+no_connect"))
    )
    (net (code "92") (name "unconnected-(U1-PA11{slash}CAN_RX{slash}USBDM{slash}TIM1_CH4-Pad44)") (class "Default")
      (node (ref "U1") (pin "44") (pinfunction "PA11/CAN_RX/USBDM/TIM1_CH4_44") (pintype "passive+no_connect"))
    )
    (net (code "93") (name "unconnected-(U1-PA12{slash}CAN_TX{slash}USBDP{slash}TIM1_ETR-Pad45)") (class "Default")
      (node (ref "U1") (pin "45") (pinfunction "PA12/CAN_TX/USBDP/TIM1_ETR_45") (pintype "passive+no_connect"))
    )
    (net (code "94") (name "unconnected-(U1-PC9-Pad40)") (class "Default")
      (node (ref "U1") (pin "40") (pinfunction "PC9_40") (pintype "passive+no_connect"))
    )
    (net (code "95") (name "unconnected-(U1-PC13{slash}ANT1-Pad2)") (class "Default")
      (node (ref "U1") (pin "2") (pinfunction "PC13/ANT1_2") (pintype "passive+no_connect"))
    )
    (net (code "96") (name "unconnected-(U1-VBAT-Pad1)") (class "Default")
      (node (ref "U1") (pin "1") (pinfunction "VBAT_1") (pintype "passive+no_connect"))
    )
    (net (code "97") (name "unconnected-(U14-STDBY-Pad6)") (class "Default")
      (node (ref "U14") (pin "6") (pinfunction "STDBY_6") (pintype "passive"))
    )
  )
)
